# MB1134.net
KiCad netlist of a schematic drawn in Altium Designer
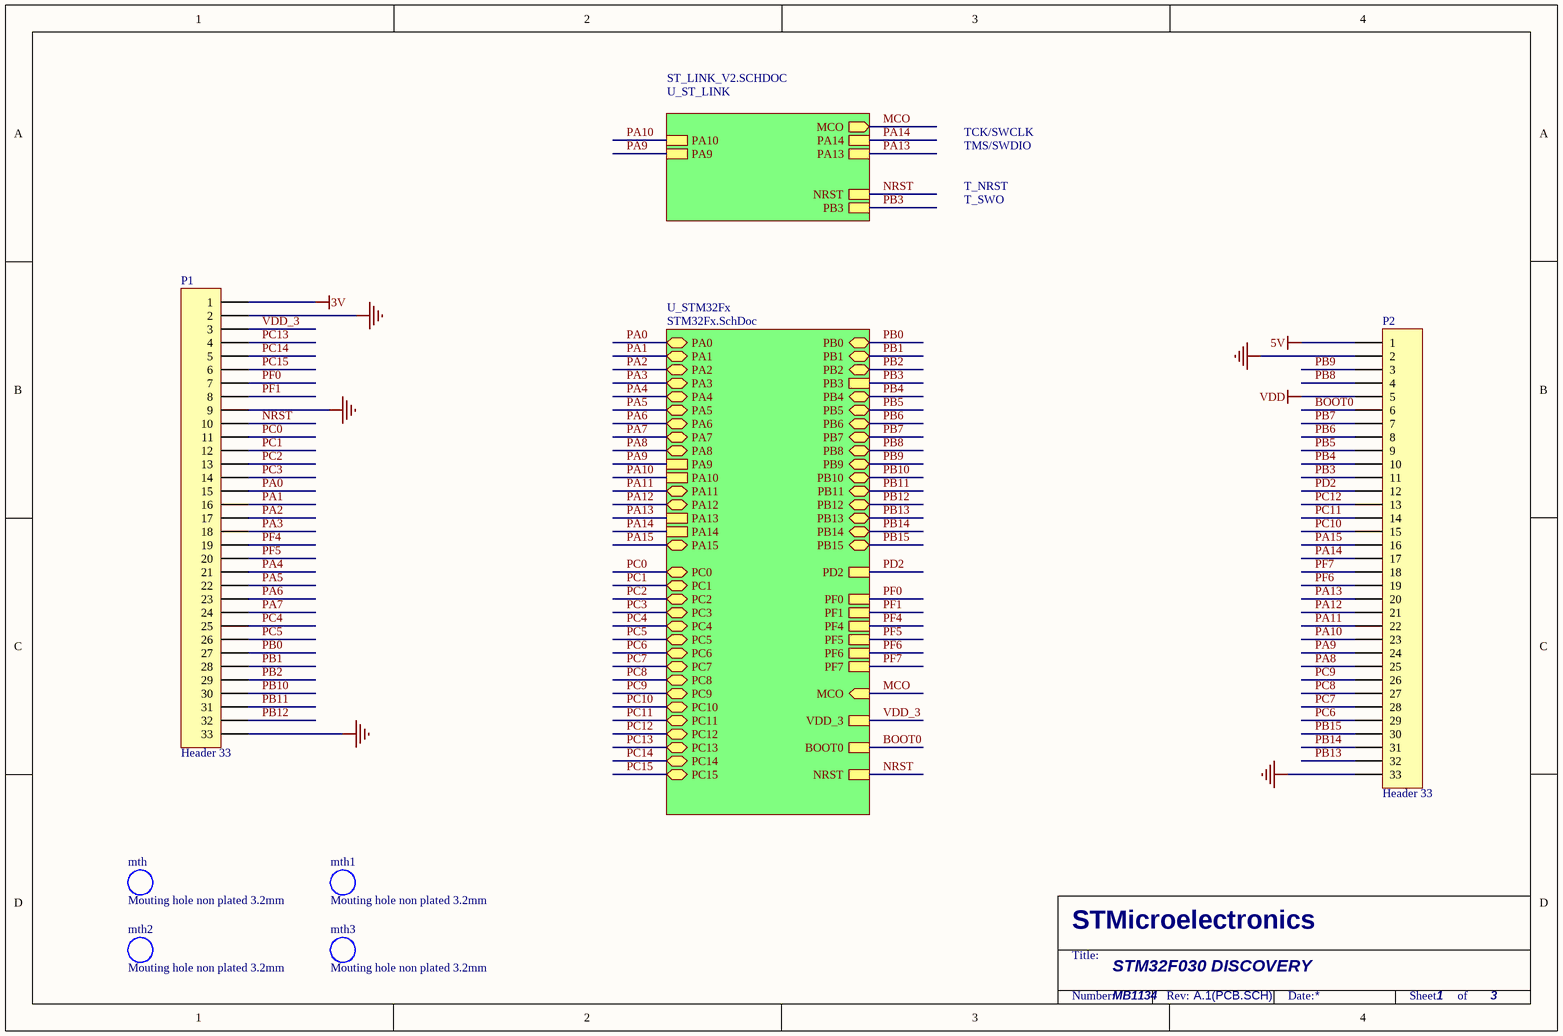
[diagram p0: MB1134.SchDoc]

(export (version "E")
  (design (tool "Eeschema 10.0.6"))
  (components
    (comp (ref "mth")
      (value "Mouting hole non plated 3.2mm")
      (footprint "mounting")
      (libsource (lib "MB1134") (part "mth"))
    )
    (comp (ref "mth1")
      (value "Mouting hole non plated 3.2mm")
      (footprint "mounting")
      (libsource (lib "MB1134") (part "mth"))
    )
    (comp (ref "mth2")
      (value "Mouting hole non plated 3.2mm")
      (footprint "mounting")
      (libsource (lib "MB1134") (part "mth"))
    )
    (comp (ref "mth3")
      (value "Mouting hole non plated 3.2mm")
      (footprint "mounting")
      (libsource (lib "MB1134") (part "mth"))
    )
    (comp (ref "P1")
      (value "Header 33")
      (footprint "SAMTEC_MTSW-133-22-S-S-400")
      (description "Header, 33-Pin")
      (fields (field (name "PUBLISHER") "Altium Limited"))
      (libsource (lib "MB1134") (part "Header 33"))
    )
    (comp (ref "P2")
      (value "Header 33")
      (footprint "SAMTEC_MTSW-133-22-S-S-400")
      (description "Header, 33-Pin")
      (fields (field (name "PUBLISHER") "Altium Limited"))
      (libsource (lib "") (part "Header 33_1"))
    )
  )
  (nets
    (net (code "1") (name "/BOOT0") (class "Default")
      (node (ref "P2") (pin "6") (pinfunction "6_6") (pintype "passive"))
    )
    (net (code "3") (name "/NRST") (class "Default")
      (node (ref "P1") (pin "10") (pinfunction "10_10") (pintype "passive"))
    )
    (net (code "4") (name "/PA0") (class "Default")
      (node (ref "P1") (pin "15") (pinfunction "15_15") (pintype "passive"))
    )
    (net (code "5") (name "/PA1") (class "Default")
      (node (ref "P1") (pin "16") (pinfunction "16_16") (pintype "passive"))
    )
    (net (code "6") (name "/PA2") (class "Default")
      (node (ref "P1") (pin "17") (pinfunction "17_17") (pintype "passive"))
    )
    (net (code "7") (name "/PA3") (class "Default")
      (node (ref "P1") (pin "18") (pinfunction "18_18") (pintype "passive"))
    )
    (net (code "8") (name "/PA4") (class "Default")
      (node (ref "P1") (pin "21") (pinfunction "21_21") (pintype "passive"))
    )
    (net (code "9") (name "/PA5") (class "Default")
      (node (ref "P1") (pin "22") (pinfunction "22_22") (pintype "passive"))
    )
    (net (code "10") (name "/PA6") (class "Default")
      (node (ref "P1") (pin "23") (pinfunction "23_23") (pintype "passive"))
    )
    (net (code "11") (name "/PA7") (class "Default")
      (node (ref "P1") (pin "24") (pinfunction "24_24") (pintype "passive"))
    )
    (net (code "12") (name "/PA8") (class "Default")
      (node (ref "P2") (pin "25") (pinfunction "25_25") (pintype "passive"))
    )
    (net (code "13") (name "/PA9") (class "Default")
      (node (ref "P2") (pin "24") (pinfunction "24_24") (pintype "passive"))
    )
    (net (code "14") (name "/PA10") (class "Default")
      (node (ref "P2") (pin "23") (pinfunction "23_23") (pintype "passive"))
    )
    (net (code "15") (name "/PA11") (class "Default")
      (node (ref "P2") (pin "22") (pinfunction "22_22") (pintype "passive"))
    )
    (net (code "16") (name "/PA12") (class "Default")
      (node (ref "P2") (pin "21") (pinfunction "21_21") (pintype "passive"))
    )
    (net (code "17") (name "/PA13") (class "Default")
      (node (ref "P2") (pin "20") (pinfunction "20_20") (pintype "passive"))
    )
    (net (code "18") (name "/PA14") (class "Default")
      (node (ref "P2") (pin "17") (pinfunction "17_17") (pintype "passive"))
    )
    (net (code "19") (name "/PA15") (class "Default")
      (node (ref "P2") (pin "16") (pinfunction "16_16") (pintype "passive"))
    )
    (net (code "20") (name "/PB0") (class "Default")
      (node (ref "P1") (pin "27") (pinfunction "27_27") (pintype "passive"))
    )
    (net (code "21") (name "/PB1") (class "Default")
      (node (ref "P1") (pin "28") (pinfunction "28_28") (pintype "passive"))
    )
    (net (code "22") (name "/PB2") (class "Default")
      (node (ref "P1") (pin "29") (pinfunction "29_29") (pintype "passive"))
    )
    (net (code "23") (name "/PB3") (class "Default")
      (node (ref "P2") (pin "11") (pinfunction "11_11") (pintype "passive"))
    )
    (net (code "24") (name "/PB4") (class "Default")
      (node (ref "P2") (pin "10") (pinfunction "10_10") (pintype "passive"))
    )
    (net (code "25") (name "/PB5") (class "Default")
      (node (ref "P2") (pin "9") (pinfunction "9_9") (pintype "passive"))
    )
    (net (code "26") (name "/PB6") (class "Default")
      (node (ref "P2") (pin "8") (pinfunction "8_8") (pintype "passive"))
    )
    (net (code "27") (name "/PB7") (class "Default")
      (node (ref "P2") (pin "7") (pinfunction "7_7") (pintype "passive"))
    )
    (net (code "28") (name "/PB8") (class "Default")
      (node (ref "P2") (pin "4") (pinfunction "4_4") (pintype "passive"))
    )
    (net (code "29") (name "/PB9") (class "Default")
      (node (ref "P2") (pin "3") (pinfunction "3_3") (pintype "passive"))
    )
    (net (code "30") (name "/PB10") (class "Default")
      (node (ref "P1") (pin "30") (pinfunction "30_30") (pintype "passive"))
    )
    (net (code "31") (name "/PB11") (class "Default")
      (node (ref "P1") (pin "31") (pinfunction "31_31") (pintype "passive"))
    )
    (net (code "32") (name "/PB12") (class "Default")
      (node (ref "P1") (pin "32") (pinfunction "32_32") (pintype "passive"))
    )
    (net (code "33") (name "/PB13") (class "Default")
      (node (ref "P2") (pin "32") (pinfunction "32_32") (pintype "passive"))
    )
    (net (code "34") (name "/PB14") (class "Default")
      (node (ref "P2") (pin "31") (pinfunction "31_31") (pintype "passive"))
    )
    (net (code "35") (name "/PB15") (class "Default")
      (node (ref "P2") (pin "30") (pinfunction "30_30") (pintype "passive"))
    )
    (net (code "36") (name "/PC0") (class "Default")
      (node (ref "P1") (pin "11") (pinfunction "11_11") (pintype "passive"))
    )
    (net (code "37") (name "/PC1") (class "Default")
      (node (ref "P1") (pin "12") (pinfunction "12_12") (pintype "passive"))
    )
    (net (code "38") (name "/PC2") (class "Default")
      (node (ref "P1") (pin "13") (pinfunction "13_13") (pintype "passive"))
    )
    (net (code "39") (name "/PC3") (class "Default")
      (node (ref "P1") (pin "14") (pinfunction "14_14") (pintype "passive"))
    )
    (net (code "40") (name "/PC4") (class "Default")
      (node (ref "P1") (pin "25") (pinfunction "25_25") (pintype "passive"))
    )
    (net (code "41") (name "/PC5") (class "Default")
      (node (ref "P1") (pin "26") (pinfunction "26_26") (pintype "passive"))
    )
    (net (code "42") (name "/PC6") (class "Default")
      (node (ref "P2") (pin "29") (pinfunction "29_29") (pintype "passive"))
    )
    (net (code "43") (name "/PC7") (class "Default")
      (node (ref "P2") (pin "28") (pinfunction "28_28") (pintype "passive"))
    )
    (net (code "44") (name "/PC8") (class "Default")
      (node (ref "P2") (pin "27") (pinfunction "27_27") (pintype "passive"))
    )
    (net (code "45") (name "/PC9") (class "Default")
      (node (ref "P2") (pin "26") (pinfunction "26_26") (pintype "passive"))
    )
    (net (code "46") (name "/PC10") (class "Default")
      (node (ref "P2") (pin "15") (pinfunction "15_15") (pintype "passive"))
    )
    (net (code "47") (name "/PC11") (class "Default")
      (node (ref "P2") (pin "14") (pinfunction "14_14") (pintype "passive"))
    )
    (net (code "48") (name "/PC12") (class "Default")
      (node (ref "P2") (pin "13") (pinfunction "13_13") (pintype "passive"))
    )
    (net (code "49") (name "/PC13") (class "Default")
      (node (ref "P1") (pin "4") (pinfunction "4_4") (pintype "passive"))
    )
    (net (code "50") (name "/PC14") (class "Default")
      (node (ref "P1") (pin "5") (pinfunction "5_5") (pintype "passive"))
    )
    (net (code "51") (name "/PC15") (class "Default")
      (node (ref "P1") (pin "6") (pinfunction "6_6") (pintype "passive"))
    )
    (net (code "52") (name "/PD2") (class "Default")
      (node (ref "P2") (pin "12") (pinfunction "12_12") (pintype "passive"))
    )
    (net (code "53") (name "/PF0") (class "Default")
      (node (ref "P1") (pin "7") (pinfunction "7_7") (pintype "passive"))
    )
    (net (code "54") (name "/PF1") (class "Default")
      (node (ref "P1") (pin "8") (pinfunction "8_8") (pintype "passive"))
    )
    (net (code "55") (name "/PF4") (class "Default")
      (node (ref "P1") (pin "19") (pinfunction "19_19") (pintype "passive"))
    )
    (net (code "56") (name "/PF5") (class "Default")
      (node (ref "P1") (pin "20") (pinfunction "20_20") (pintype "passive"))
    )
    (net (code "57") (name "/PF6") (class "Default")
      (node (ref "P2") (pin "19") (pinfunction "19_19") (pintype "passive"))
    )
    (net (code "58") (name "/PF7") (class "Default")
      (node (ref "P2") (pin "18") (pinfunction "18_18") (pintype "passive"))
    )
    (net (code "59") (name "/VDD_3") (class "Default")
      (node (ref "P1") (pin "3") (pinfunction "3_3") (pintype "passive"))
    )
    (net (code "60") (name "3V") (class "Default")
      (node (ref "P1") (pin "1") (pinfunction "1_1") (pintype "passive"))
    )
    (net (code "61") (name "5V") (class "Default")
      (node (ref "P2") (pin "1") (pinfunction "1_1") (pintype "passive"))
    )
    (net (code "62") (name "GND") (class "Default")
      (node (ref "P1") (pin "2") (pinfunction "2_2") (pintype "passive"))
      (node (ref "P1") (pin "33") (pinfunction "33_33") (pintype "passive"))
      (node (ref "P1") (pin "9") (pinfunction "9_9") (pintype "passive"))
      (node (ref "P2") (pin "2") (pinfunction "2_2") (pintype "passive"))
      (node (ref "P2") (pin "33") (pinfunction "33_33") (pintype "passive"))
    )
    (net (code "63") (name "VDD") (class "Default")
      (node (ref "P2") (pin "5") (pinfunction "5_5") (pintype "passive"))
    )
  )
)
